# logic-UHF.net
KiCad netlist of a schematic drawn in EAGLE
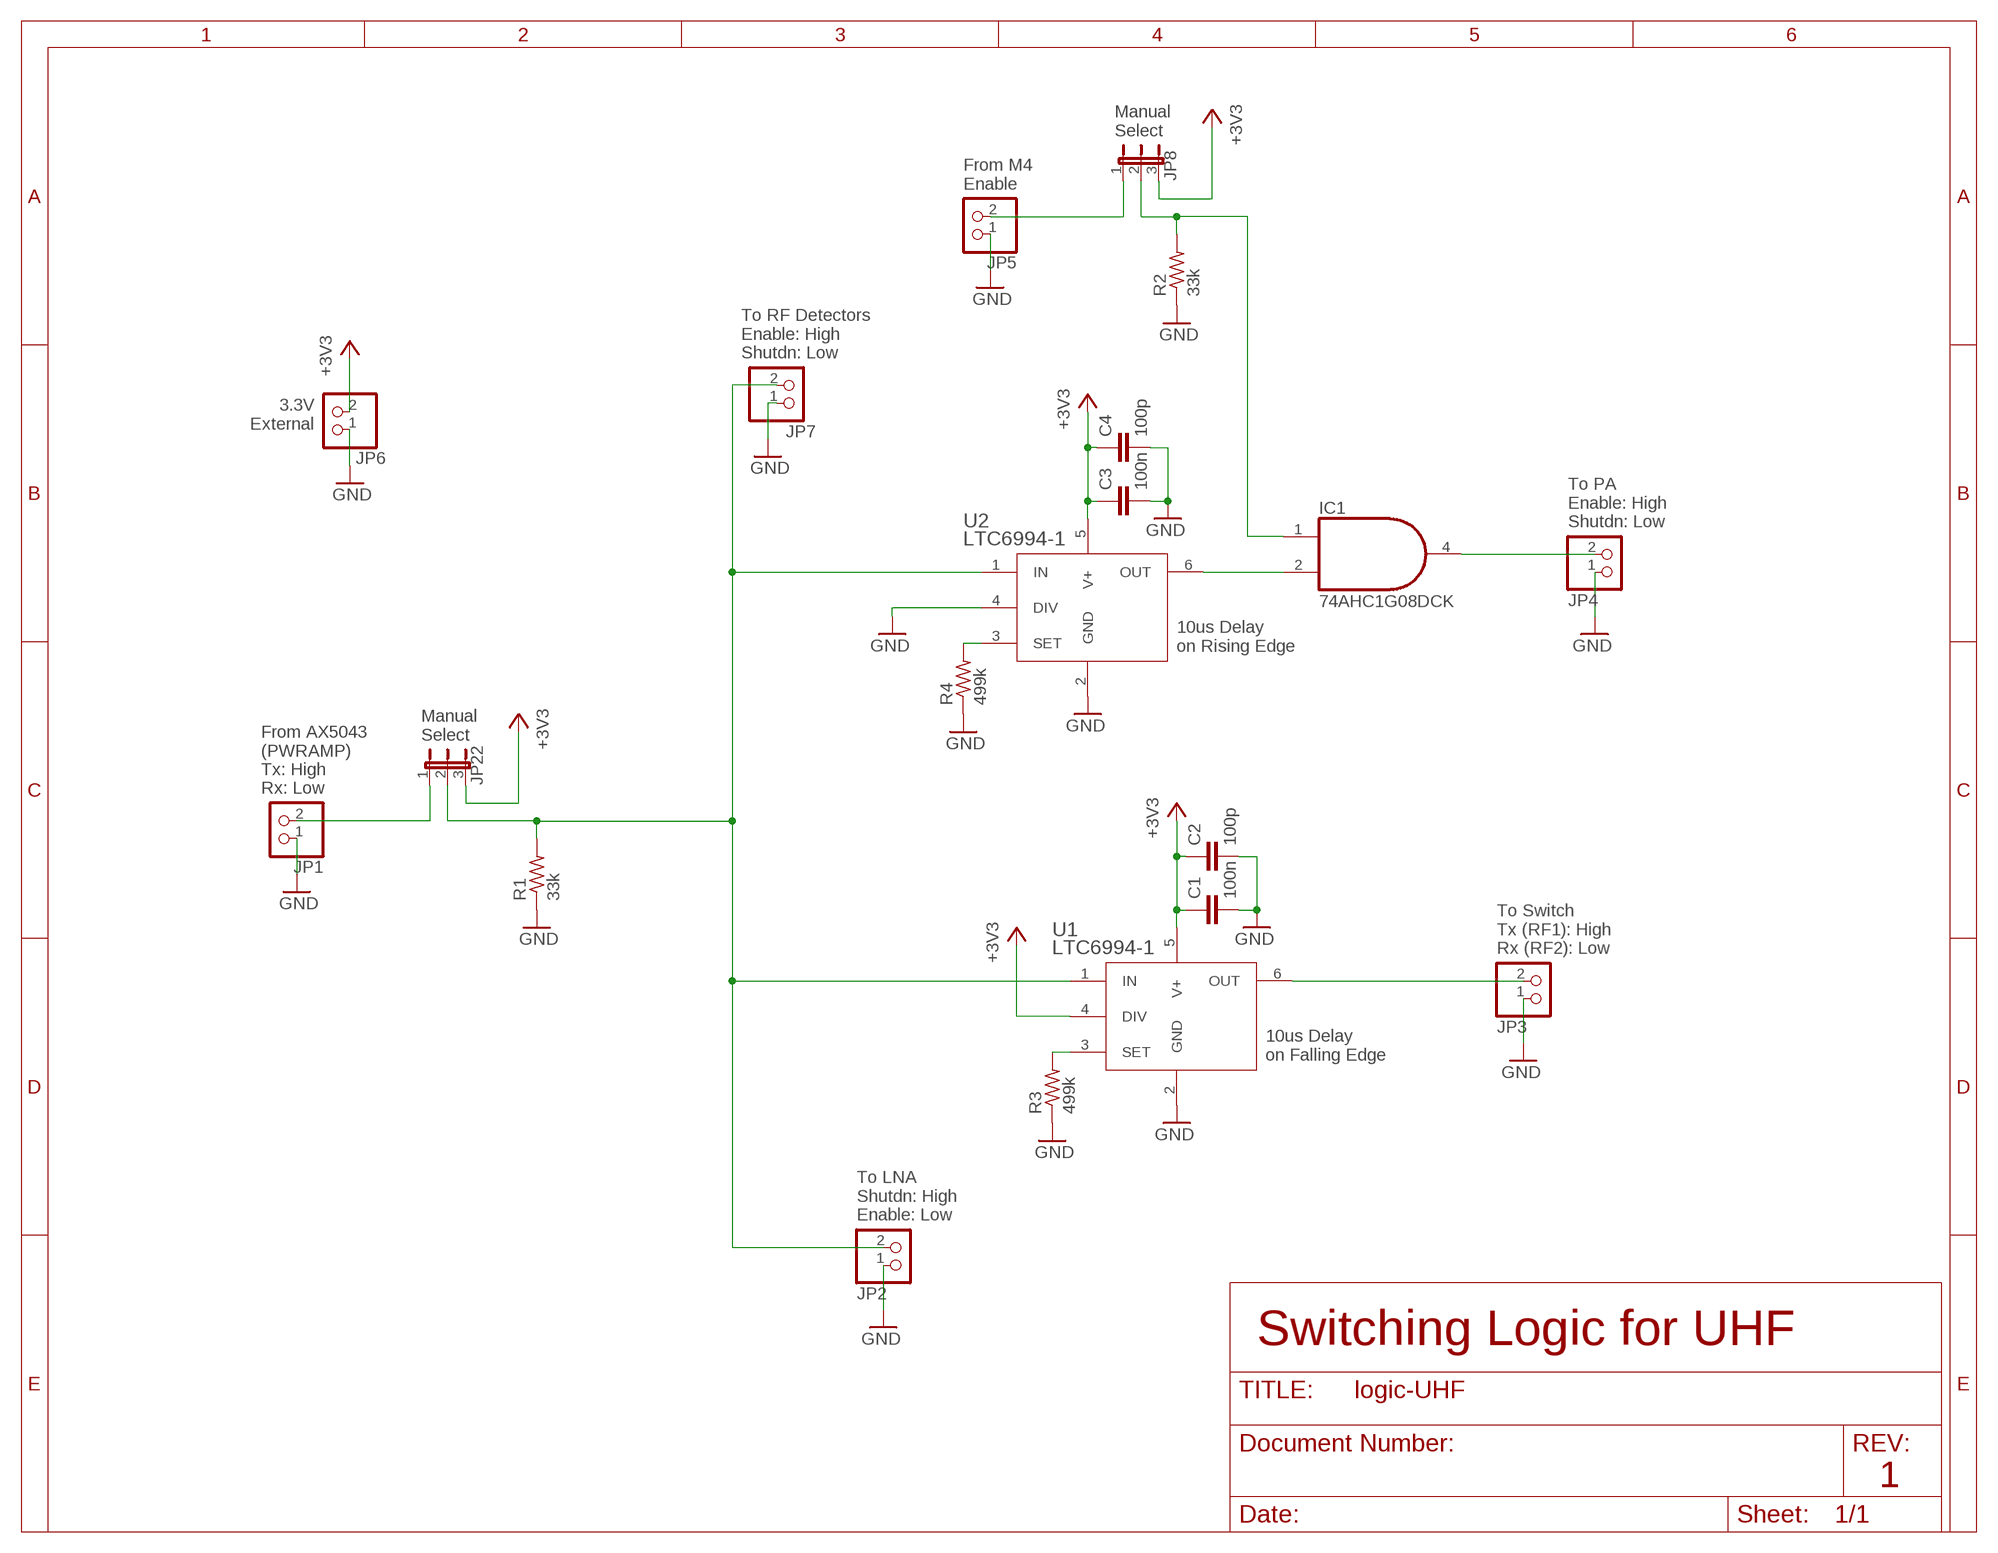
[diagram p0: schematic, sheet 1]

(export (version "E")
  (design (tool "Eeschema 10.0.6"))
  (components
    (comp (ref "C1")
      (value "100n")
      (footprint "eagle-import:.0603-B-NOSILK")
      (libsource (lib "eagle-import") (part "C-EU0603-B-NOSILK"))
    )
    (comp (ref "C2")
      (value "100p")
      (footprint "eagle-import:.0603-B-NOSILK")
      (libsource (lib "eagle-import") (part "C-EU0603-B-NOSILK"))
    )
    (comp (ref "C3")
      (value "100n")
      (footprint "eagle-import:.0603-B-NOSILK")
      (libsource (lib "eagle-import") (part "C-EU0603-B-NOSILK"))
    )
    (comp (ref "C4")
      (value "100p")
      (footprint "eagle-import:.0603-B-NOSILK")
      (libsource (lib "eagle-import") (part "C-EU0603-B-NOSILK"))
    )
    (comp (ref "IC1")
      (value "74AHC1G08DCK")
      (footprint "eagle-import:SC70-5")
      (libsource (lib "eagle-import") (part "741G08DCKAHC"))
    )
    (comp (ref "JP1")
      (value "PINHD-1X2")
      (footprint "eagle-import:1X02")
      (libsource (lib "eagle-import") (part "PINHD-1X2"))
    )
    (comp (ref "JP2")
      (value "PINHD-1X2")
      (footprint "eagle-import:1X02")
      (libsource (lib "eagle-import") (part "PINHD-1X2"))
    )
    (comp (ref "JP3")
      (value "PINHD-1X2")
      (footprint "eagle-import:1X02")
      (libsource (lib "eagle-import") (part "PINHD-1X2"))
    )
    (comp (ref "JP4")
      (value "PINHD-1X2")
      (footprint "eagle-import:1X02")
      (libsource (lib "eagle-import") (part "PINHD-1X2"))
    )
    (comp (ref "JP5")
      (value "PINHD-1X2")
      (footprint "eagle-import:1X02")
      (libsource (lib "eagle-import") (part "PINHD-1X2"))
    )
    (comp (ref "JP6")
      (value "PINHD-1X2")
      (footprint "eagle-import:1X02")
      (libsource (lib "eagle-import") (part "PINHD-1X2"))
    )
    (comp (ref "JP7")
      (value "PINHD-1X2")
      (footprint "eagle-import:1X02")
      (libsource (lib "eagle-import") (part "PINHD-1X2"))
    )
    (comp (ref "JP8")
      (value "JP2E")
      (footprint "eagle-import:JP2")
      (libsource (lib "eagle-import") (part "JP2E"))
    )
    (comp (ref "JP22")
      (value "JP2E")
      (footprint "eagle-import:JP2")
      (libsource (lib "eagle-import") (part "JP2E"))
    )
    (comp (ref "R1")
      (value "33k")
      (footprint "eagle-import:.0603-B-NOSILK")
      (libsource (lib "eagle-import") (part "R-US_0603-B-NOSILK"))
    )
    (comp (ref "R2")
      (value "33k")
      (footprint "eagle-import:.0603-B-NOSILK")
      (libsource (lib "eagle-import") (part "R-US_0603-B-NOSILK"))
    )
    (comp (ref "R3")
      (value "499k")
      (footprint "eagle-import:.0603-B-NOSILK")
      (libsource (lib "eagle-import") (part "R-US_0603-B-NOSILK"))
    )
    (comp (ref "R4")
      (value "499k")
      (footprint "eagle-import:.0603-B-NOSILK")
      (libsource (lib "eagle-import") (part "R-US_0603-B-NOSILK"))
    )
    (comp (ref "U1")
      (value "LTC6994-1")
      (footprint "eagle-import:TSOT-23_S6")
      (fields (field (name "MFR") "Linear Technology"))
      (libsource (lib "eagle-import") (part "LTC6994CS6-1PBF"))
    )
    (comp (ref "U2")
      (value "LTC6994-1")
      (footprint "eagle-import:TSOT-23_S6")
      (fields (field (name "MFR") "Linear Technology"))
      (libsource (lib "eagle-import") (part "LTC6994CS6-1PBF"))
    )
  )
  (nets
    (net (code "1") (name "+3V3") (class "Default")
      (node (ref "C1") (pin "1") (pinfunction "1_1") (pintype "passive"))
      (node (ref "C2") (pin "1") (pinfunction "1_1") (pintype "passive"))
      (node (ref "C3") (pin "1") (pinfunction "1_1") (pintype "passive"))
      (node (ref "C4") (pin "1") (pinfunction "1_1") (pintype "passive"))
      (node (ref "JP22") (pin "3") (pinfunction "3_3") (pintype "passive"))
      (node (ref "JP6") (pin "2") (pinfunction "2_2") (pintype "passive"))
      (node (ref "JP8") (pin "3") (pinfunction "3_3") (pintype "passive"))
      (node (ref "U1") (pin "4") (pinfunction "DIV_4") (pintype "input"))
      (node (ref "U1") (pin "5") (pinfunction "V+_5") (pintype "power_in"))
      (node (ref "U2") (pin "5") (pinfunction "V+_5") (pintype "power_in"))
    )
    (net (code "2") (name "GND") (class "Default")
      (node (ref "C1") (pin "2") (pinfunction "2_2") (pintype "passive"))
      (node (ref "C2") (pin "2") (pinfunction "2_2") (pintype "passive"))
      (node (ref "C3") (pin "2") (pinfunction "2_2") (pintype "passive"))
      (node (ref "C4") (pin "2") (pinfunction "2_2") (pintype "passive"))
      (node (ref "JP1") (pin "1") (pinfunction "1_1") (pintype "passive"))
      (node (ref "JP2") (pin "1") (pinfunction "1_1") (pintype "passive"))
      (node (ref "JP3") (pin "1") (pinfunction "1_1") (pintype "passive"))
      (node (ref "JP4") (pin "1") (pinfunction "1_1") (pintype "passive"))
      (node (ref "JP5") (pin "1") (pinfunction "1_1") (pintype "passive"))
      (node (ref "JP6") (pin "1") (pinfunction "1_1") (pintype "passive"))
      (node (ref "JP7") (pin "1") (pinfunction "1_1") (pintype "passive"))
      (node (ref "R1") (pin "1") (pinfunction "1_1") (pintype "passive"))
      (node (ref "R2") (pin "1") (pinfunction "1_1") (pintype "passive"))
      (node (ref "R3") (pin "1") (pinfunction "1_1") (pintype "passive"))
      (node (ref "R4") (pin "1") (pinfunction "1_1") (pintype "passive"))
      (node (ref "U1") (pin "2") (pinfunction "GND_2") (pintype "power_in"))
      (node (ref "U2") (pin "2") (pinfunction "GND_2") (pintype "power_in"))
      (node (ref "U2") (pin "4") (pinfunction "DIV_4") (pintype "input"))
    )
    (net (code "3") (name "Net-(IC1A-I0)") (class "Default")
      (node (ref "IC1") (pin "1") (pinfunction "I0_1") (pintype "input"))
      (node (ref "JP8") (pin "2") (pinfunction "2_2") (pintype "passive"))
      (node (ref "R2") (pin "2") (pinfunction "2_2") (pintype "passive"))
    )
    (net (code "4") (name "Net-(IC1A-I1)") (class "Default")
      (node (ref "IC1") (pin "2") (pinfunction "I1_2") (pintype "input"))
      (node (ref "U2") (pin "6") (pinfunction "OUT_6") (pintype "output"))
    )
    (net (code "5") (name "Net-(IC1A-O)") (class "Default")
      (node (ref "IC1") (pin "4") (pinfunction "O_4") (pintype "output"))
      (node (ref "JP4") (pin "2") (pinfunction "2_2") (pintype "passive"))
    )
    (net (code "6") (name "Net-(JP1-Pad2)") (class "Default")
      (node (ref "JP1") (pin "2") (pinfunction "2_2") (pintype "passive"))
      (node (ref "JP22") (pin "1") (pinfunction "1_1") (pintype "passive"))
    )
    (net (code "7") (name "Net-(JP5-Pad2)") (class "Default")
      (node (ref "JP5") (pin "2") (pinfunction "2_2") (pintype "passive"))
      (node (ref "JP8") (pin "1") (pinfunction "1_1") (pintype "passive"))
    )
    (net (code "8") (name "Net-(U1-IN)") (class "Default")
      (node (ref "JP2") (pin "2") (pinfunction "2_2") (pintype "passive"))
      (node (ref "JP22") (pin "2") (pinfunction "2_2") (pintype "passive"))
      (node (ref "JP7") (pin "2") (pinfunction "2_2") (pintype "passive"))
      (node (ref "R1") (pin "2") (pinfunction "2_2") (pintype "passive"))
      (node (ref "U1") (pin "1") (pinfunction "IN_1") (pintype "input"))
      (node (ref "U2") (pin "1") (pinfunction "IN_1") (pintype "input"))
    )
    (net (code "9") (name "Net-(U1-OUT)") (class "Default")
      (node (ref "JP3") (pin "2") (pinfunction "2_2") (pintype "passive"))
      (node (ref "U1") (pin "6") (pinfunction "OUT_6") (pintype "output"))
    )
    (net (code "10") (name "Net-(U1-SET)") (class "Default")
      (node (ref "R3") (pin "2") (pinfunction "2_2") (pintype "passive"))
      (node (ref "U1") (pin "3") (pinfunction "SET_3") (pintype "input"))
    )
    (net (code "11") (name "Net-(U2-SET)") (class "Default")
      (node (ref "R4") (pin "2") (pinfunction "2_2") (pintype "passive"))
      (node (ref "U2") (pin "3") (pinfunction "SET_3") (pintype "input"))
    )
  )
)
